# mouthbrain.net
KiCad netlist of a schematic drawn in EAGLE
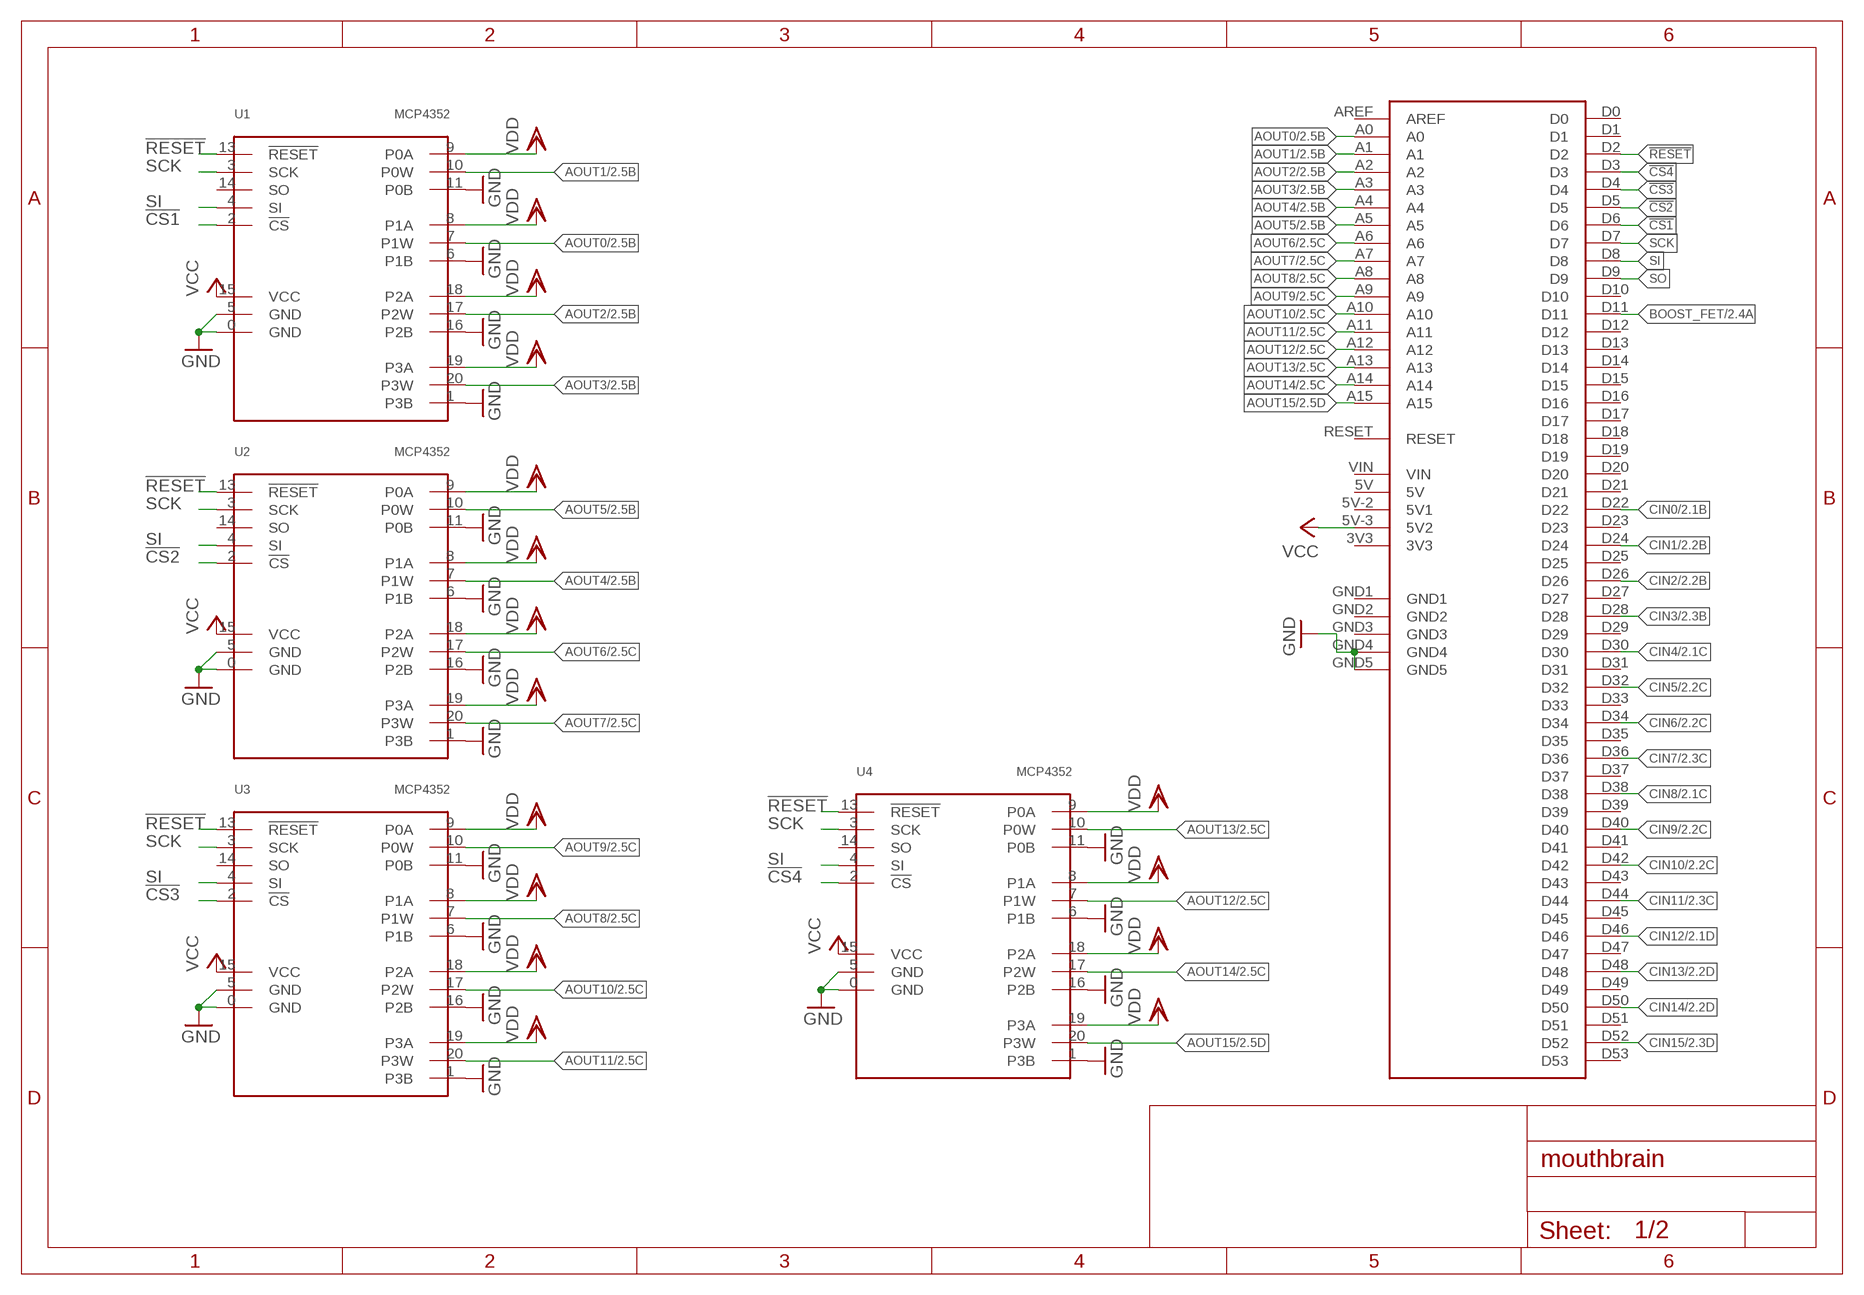
[diagram p0: schematic, sheet 1]
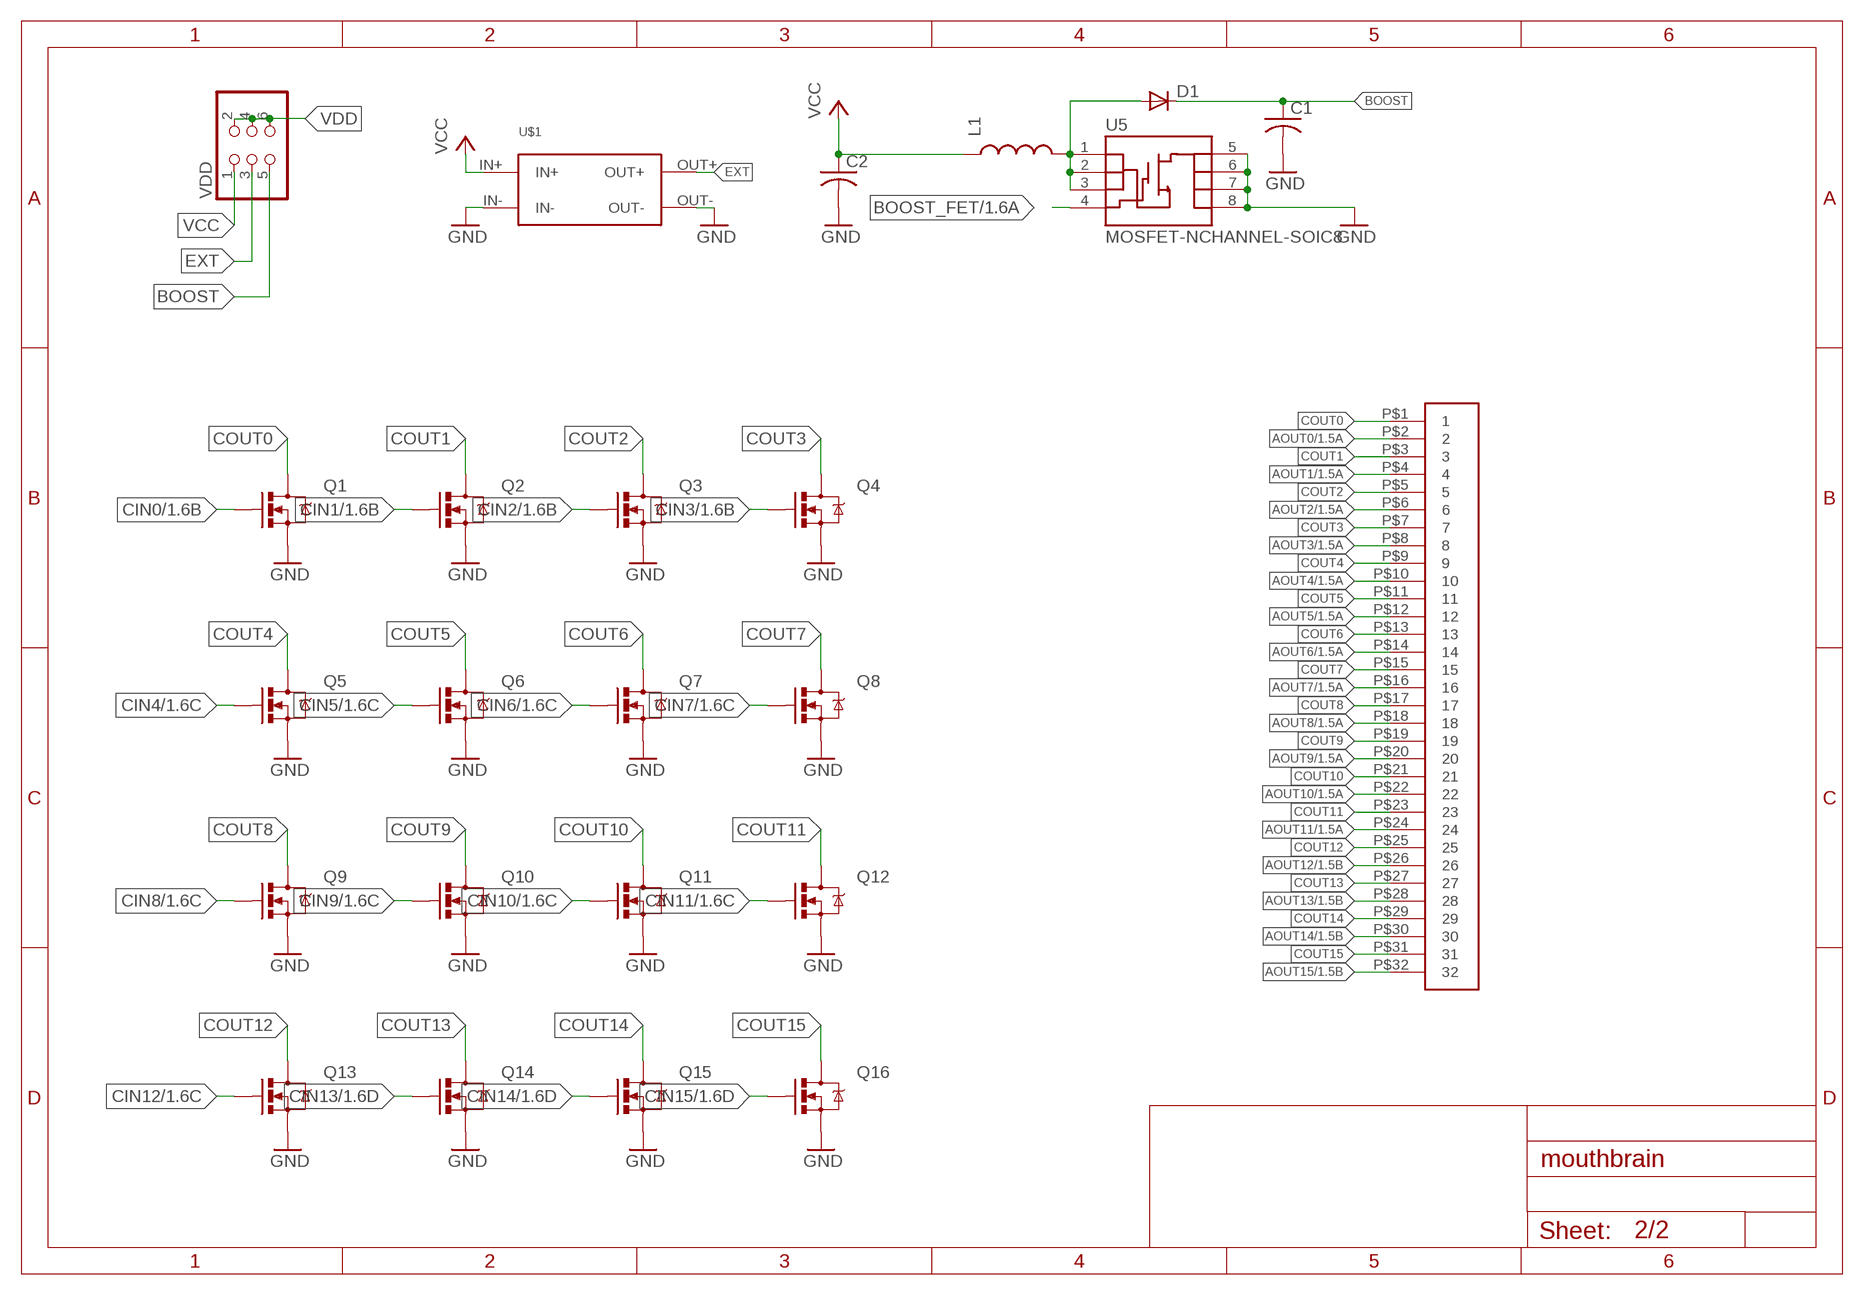
[diagram p1: schematic, sheet 2]

(export (version "E")
  (design (tool "Eeschema 10.0.6"))
  (components
    (comp (ref "C1")
      (value "C-USC1206")
      (footprint "eagle-import:C1206")
      (libsource (lib "eagle-import") (part "C-USC1206"))
    )
    (comp (ref "C2")
      (value "C-USC1206")
      (footprint "eagle-import:C1206")
      (libsource (lib "eagle-import") (part "C-USC1206"))
    )
    (comp (ref "D1")
      (value "DIODESMA")
      (footprint "eagle-import:SMA-DIODE")
      (libsource (lib "eagle-import") (part "DIODESMA"))
    )
    (comp (ref "L1")
      (value "INDUCTOR1206H*")
      (footprint "eagle-import:INDUCTOR-1206")
      (libsource (lib "eagle-import") (part "INDUCTORH1206"))
    )
    (comp (ref "Q1")
      (value "MOSFET-NCHANNELSMD")
      (footprint "eagle-import:SOT23-3")
      (libsource (lib "eagle-import") (part "MOSFET-NCHANNELSMD"))
    )
    (comp (ref "Q2")
      (value "MOSFET-NCHANNELSMD")
      (footprint "eagle-import:SOT23-3")
      (libsource (lib "eagle-import") (part "MOSFET-NCHANNELSMD"))
    )
    (comp (ref "Q3")
      (value "MOSFET-NCHANNELSMD")
      (footprint "eagle-import:SOT23-3")
      (libsource (lib "eagle-import") (part "MOSFET-NCHANNELSMD"))
    )
    (comp (ref "Q4")
      (value "MOSFET-NCHANNELSMD")
      (footprint "eagle-import:SOT23-3")
      (libsource (lib "eagle-import") (part "MOSFET-NCHANNELSMD"))
    )
    (comp (ref "Q5")
      (value "MOSFET-NCHANNELSMD")
      (footprint "eagle-import:SOT23-3")
      (libsource (lib "eagle-import") (part "MOSFET-NCHANNELSMD"))
    )
    (comp (ref "Q6")
      (value "MOSFET-NCHANNELSMD")
      (footprint "eagle-import:SOT23-3")
      (libsource (lib "eagle-import") (part "MOSFET-NCHANNELSMD"))
    )
    (comp (ref "Q7")
      (value "MOSFET-NCHANNELSMD")
      (footprint "eagle-import:SOT23-3")
      (libsource (lib "eagle-import") (part "MOSFET-NCHANNELSMD"))
    )
    (comp (ref "Q8")
      (value "MOSFET-NCHANNELSMD")
      (footprint "eagle-import:SOT23-3")
      (libsource (lib "eagle-import") (part "MOSFET-NCHANNELSMD"))
    )
    (comp (ref "Q9")
      (value "MOSFET-NCHANNELSMD")
      (footprint "eagle-import:SOT23-3")
      (libsource (lib "eagle-import") (part "MOSFET-NCHANNELSMD"))
    )
    (comp (ref "Q10")
      (value "MOSFET-NCHANNELSMD")
      (footprint "eagle-import:SOT23-3")
      (libsource (lib "eagle-import") (part "MOSFET-NCHANNELSMD"))
    )
    (comp (ref "Q11")
      (value "MOSFET-NCHANNELSMD")
      (footprint "eagle-import:SOT23-3")
      (libsource (lib "eagle-import") (part "MOSFET-NCHANNELSMD"))
    )
    (comp (ref "Q12")
      (value "MOSFET-NCHANNELSMD")
      (footprint "eagle-import:SOT23-3")
      (libsource (lib "eagle-import") (part "MOSFET-NCHANNELSMD"))
    )
    (comp (ref "Q13")
      (value "MOSFET-NCHANNELSMD")
      (footprint "eagle-import:SOT23-3")
      (libsource (lib "eagle-import") (part "MOSFET-NCHANNELSMD"))
    )
    (comp (ref "Q14")
      (value "MOSFET-NCHANNELSMD")
      (footprint "eagle-import:SOT23-3")
      (libsource (lib "eagle-import") (part "MOSFET-NCHANNELSMD"))
    )
    (comp (ref "Q15")
      (value "MOSFET-NCHANNELSMD")
      (footprint "eagle-import:SOT23-3")
      (libsource (lib "eagle-import") (part "MOSFET-NCHANNELSMD"))
    )
    (comp (ref "Q16")
      (value "MOSFET-NCHANNELSMD")
      (footprint "eagle-import:SOT23-3")
      (libsource (lib "eagle-import") (part "MOSFET-NCHANNELSMD"))
    )
    (comp (ref "U$1")
      (value "DC-DC-CONVERTER")
      (footprint "eagle-import:DC-DC-MODULE")
      (libsource (lib "eagle-import") (part "DC-DC-CONVERTER"))
    )
    (comp (ref "U$2")
      (value "FPC-0.5-32HORIZ")
      (footprint "eagle-import:FPC-32-HORIZONTAL")
      (libsource (lib "eagle-import") (part "FPC-0.5-32HORIZ"))
    )
    (comp (ref "U5")
      (value "MOSFET-NCHANNEL-SOIC8")
      (footprint "eagle-import:SO08")
      (libsource (lib "eagle-import") (part "MOSFET-NCHANNEL-SOIC8"))
    )
    (comp (ref "VDD")
      (value "PINHD-2X3")
      (footprint "eagle-import:2X03")
      (libsource (lib "eagle-import") (part "PINHD-2X3"))
    )
    (comp (ref "U$3")
      (value "ARDUINO-MEGA")
      (footprint "eagle-import:ARDUINO-MEGA")
      (libsource (lib "eagle-import") (part "ARDUINO-MEGA"))
    )
    (comp (ref "U1")
      (value "MCP4352")
      (footprint "eagle-import:QFN-20-PAD")
      (libsource (lib "eagle-import") (part "MCP4352"))
    )
    (comp (ref "U2")
      (value "MCP4352")
      (footprint "eagle-import:QFN-20-PAD")
      (libsource (lib "eagle-import") (part "MCP4352"))
    )
    (comp (ref "U3")
      (value "MCP4352")
      (footprint "eagle-import:QFN-20-PAD")
      (libsource (lib "eagle-import") (part "MCP4352"))
    )
    (comp (ref "U4")
      (value "MCP4352")
      (footprint "eagle-import:QFN-20-PAD")
      (libsource (lib "eagle-import") (part "MCP4352"))
    )
  )
  (nets
    (net (code "1") (name "AOUT0") (class "Default")
      (node (ref "U$2") (pin "P$2") (pinfunction "2_P$2") (pintype "bidirectional"))
      (node (ref "U$3") (pin "A0") (pinfunction "A0_A0") (pintype "bidirectional"))
      (node (ref "U1") (pin "7") (pinfunction "P1W_7") (pintype "bidirectional"))
    )
    (net (code "2") (name "AOUT1") (class "Default")
      (node (ref "U$2") (pin "P$4") (pinfunction "4_P$4") (pintype "bidirectional"))
      (node (ref "U$3") (pin "A1") (pinfunction "A1_A1") (pintype "bidirectional"))
      (node (ref "U1") (pin "10") (pinfunction "P0W_10") (pintype "bidirectional"))
    )
    (net (code "3") (name "AOUT2") (class "Default")
      (node (ref "U$2") (pin "P$6") (pinfunction "6_P$6") (pintype "bidirectional"))
      (node (ref "U$3") (pin "A2") (pinfunction "A2_A2") (pintype "bidirectional"))
      (node (ref "U1") (pin "17") (pinfunction "P2W_17") (pintype "bidirectional"))
    )
    (net (code "4") (name "AOUT3") (class "Default")
      (node (ref "U$2") (pin "P$8") (pinfunction "8_P$8") (pintype "bidirectional"))
      (node (ref "U$3") (pin "A3") (pinfunction "A3_A3") (pintype "bidirectional"))
      (node (ref "U1") (pin "20") (pinfunction "P3W_20") (pintype "bidirectional"))
    )
    (net (code "5") (name "AOUT4") (class "Default")
      (node (ref "U$2") (pin "P$10") (pinfunction "10_P$10") (pintype "bidirectional"))
      (node (ref "U$3") (pin "A4") (pinfunction "A4_A4") (pintype "bidirectional"))
      (node (ref "U2") (pin "7") (pinfunction "P1W_7") (pintype "bidirectional"))
    )
    (net (code "6") (name "AOUT5") (class "Default")
      (node (ref "U$2") (pin "P$12") (pinfunction "12_P$12") (pintype "bidirectional"))
      (node (ref "U$3") (pin "A5") (pinfunction "A5_A5") (pintype "bidirectional"))
      (node (ref "U2") (pin "10") (pinfunction "P0W_10") (pintype "bidirectional"))
    )
    (net (code "7") (name "AOUT6") (class "Default")
      (node (ref "U$2") (pin "P$14") (pinfunction "14_P$14") (pintype "bidirectional"))
      (node (ref "U$3") (pin "A6") (pinfunction "A6_A6") (pintype "bidirectional"))
      (node (ref "U2") (pin "17") (pinfunction "P2W_17") (pintype "bidirectional"))
    )
    (net (code "8") (name "AOUT7") (class "Default")
      (node (ref "U$2") (pin "P$16") (pinfunction "16_P$16") (pintype "bidirectional"))
      (node (ref "U$3") (pin "A7") (pinfunction "A7_A7") (pintype "bidirectional"))
      (node (ref "U2") (pin "20") (pinfunction "P3W_20") (pintype "bidirectional"))
    )
    (net (code "9") (name "AOUT8") (class "Default")
      (node (ref "U$2") (pin "P$18") (pinfunction "18_P$18") (pintype "bidirectional"))
      (node (ref "U$3") (pin "A8") (pinfunction "A8_A8") (pintype "bidirectional"))
      (node (ref "U3") (pin "7") (pinfunction "P1W_7") (pintype "bidirectional"))
    )
    (net (code "10") (name "AOUT9") (class "Default")
      (node (ref "U$2") (pin "P$20") (pinfunction "20_P$20") (pintype "bidirectional"))
      (node (ref "U$3") (pin "A9") (pinfunction "A9_A9") (pintype "bidirectional"))
      (node (ref "U3") (pin "10") (pinfunction "P0W_10") (pintype "bidirectional"))
    )
    (net (code "11") (name "AOUT10") (class "Default")
      (node (ref "U$2") (pin "P$22") (pinfunction "22_P$22") (pintype "bidirectional"))
      (node (ref "U$3") (pin "A10") (pinfunction "A10_A10") (pintype "bidirectional"))
      (node (ref "U3") (pin "17") (pinfunction "P2W_17") (pintype "bidirectional"))
    )
    (net (code "12") (name "AOUT11") (class "Default")
      (node (ref "U$2") (pin "P$24") (pinfunction "24_P$24") (pintype "bidirectional"))
      (node (ref "U$3") (pin "A11") (pinfunction "A11_A11") (pintype "bidirectional"))
      (node (ref "U3") (pin "20") (pinfunction "P3W_20") (pintype "bidirectional"))
    )
    (net (code "13") (name "AOUT12") (class "Default")
      (node (ref "U$2") (pin "P$26") (pinfunction "26_P$26") (pintype "bidirectional"))
      (node (ref "U$3") (pin "A12") (pinfunction "A12_A12") (pintype "bidirectional"))
      (node (ref "U4") (pin "7") (pinfunction "P1W_7") (pintype "bidirectional"))
    )
    (net (code "14") (name "AOUT13") (class "Default")
      (node (ref "U$2") (pin "P$28") (pinfunction "28_P$28") (pintype "bidirectional"))
      (node (ref "U$3") (pin "A13") (pinfunction "A13_A13") (pintype "bidirectional"))
      (node (ref "U4") (pin "10") (pinfunction "P0W_10") (pintype "bidirectional"))
    )
    (net (code "15") (name "AOUT14") (class "Default")
      (node (ref "U$2") (pin "P$30") (pinfunction "30_P$30") (pintype "bidirectional"))
      (node (ref "U$3") (pin "A14") (pinfunction "A14_A14") (pintype "bidirectional"))
      (node (ref "U4") (pin "17") (pinfunction "P2W_17") (pintype "bidirectional"))
    )
    (net (code "16") (name "AOUT15") (class "Default")
      (node (ref "U$2") (pin "P$32") (pinfunction "32_P$32") (pintype "bidirectional"))
      (node (ref "U$3") (pin "A15") (pinfunction "A15_A15") (pintype "bidirectional"))
      (node (ref "U4") (pin "20") (pinfunction "P3W_20") (pintype "bidirectional"))
    )
    (net (code "17") (name "BOOST") (class "Default")
      (node (ref "C1") (pin "1") (pinfunction "1_1") (pintype "passive"))
      (node (ref "D1") (pin "C") (pinfunction "C_C") (pintype "passive"))
      (node (ref "VDD") (pin "5") (pinfunction "5_5") (pintype "passive"))
    )
    (net (code "18") (name "BOOST_FET") (class "Default")
      (node (ref "U$3") (pin "D11") (pinfunction "D11_D11") (pintype "bidirectional"))
      (node (ref "U5") (pin "4") (pinfunction "G_4") (pintype "bidirectional"))
    )
    (net (code "19") (name "CIN0") (class "Default")
      (node (ref "Q1") (pin "1") (pinfunction "G_1") (pintype "passive"))
      (node (ref "U$3") (pin "D22") (pinfunction "D22_D22") (pintype "bidirectional"))
    )
    (net (code "20") (name "CIN1") (class "Default")
      (node (ref "Q2") (pin "1") (pinfunction "G_1") (pintype "passive"))
      (node (ref "U$3") (pin "D24") (pinfunction "D24_D24") (pintype "bidirectional"))
    )
    (net (code "21") (name "CIN2") (class "Default")
      (node (ref "Q3") (pin "1") (pinfunction "G_1") (pintype "passive"))
      (node (ref "U$3") (pin "D26") (pinfunction "D26_D26") (pintype "bidirectional"))
    )
    (net (code "22") (name "CIN3") (class "Default")
      (node (ref "Q4") (pin "1") (pinfunction "G_1") (pintype "passive"))
      (node (ref "U$3") (pin "D28") (pinfunction "D28_D28") (pintype "bidirectional"))
    )
    (net (code "23") (name "CIN4") (class "Default")
      (node (ref "Q5") (pin "1") (pinfunction "G_1") (pintype "passive"))
      (node (ref "U$3") (pin "D30") (pinfunction "D30_D30") (pintype "bidirectional"))
    )
    (net (code "24") (name "CIN5") (class "Default")
      (node (ref "Q6") (pin "1") (pinfunction "G_1") (pintype "passive"))
      (node (ref "U$3") (pin "D32") (pinfunction "D32_D32") (pintype "bidirectional"))
    )
    (net (code "25") (name "CIN6") (class "Default")
      (node (ref "Q7") (pin "1") (pinfunction "G_1") (pintype "passive"))
      (node (ref "U$3") (pin "D34") (pinfunction "D34_D34") (pintype "bidirectional"))
    )
    (net (code "26") (name "CIN7") (class "Default")
      (node (ref "Q8") (pin "1") (pinfunction "G_1") (pintype "passive"))
      (node (ref "U$3") (pin "D36") (pinfunction "D36_D36") (pintype "bidirectional"))
    )
    (net (code "27") (name "CIN8") (class "Default")
      (node (ref "Q9") (pin "1") (pinfunction "G_1") (pintype "passive"))
      (node (ref "U$3") (pin "D38") (pinfunction "D38_D38") (pintype "bidirectional"))
    )
    (net (code "28") (name "CIN9") (class "Default")
      (node (ref "Q10") (pin "1") (pinfunction "G_1") (pintype "passive"))
      (node (ref "U$3") (pin "D40") (pinfunction "D40_D40") (pintype "bidirectional"))
    )
    (net (code "29") (name "CIN10") (class "Default")
      (node (ref "Q11") (pin "1") (pinfunction "G_1") (pintype "passive"))
      (node (ref "U$3") (pin "D42") (pinfunction "D42_D42") (pintype "bidirectional"))
    )
    (net (code "30") (name "CIN11") (class "Default")
      (node (ref "Q12") (pin "1") (pinfunction "G_1") (pintype "passive"))
      (node (ref "U$3") (pin "D44") (pinfunction "D44_D44") (pintype "bidirectional"))
    )
    (net (code "31") (name "CIN12") (class "Default")
      (node (ref "Q13") (pin "1") (pinfunction "G_1") (pintype "passive"))
      (node (ref "U$3") (pin "D46") (pinfunction "D46_D46") (pintype "bidirectional"))
    )
    (net (code "32") (name "CIN13") (class "Default")
      (node (ref "Q14") (pin "1") (pinfunction "G_1") (pintype "passive"))
      (node (ref "U$3") (pin "D48") (pinfunction "D48_D48") (pintype "bidirectional"))
    )
    (net (code "33") (name "CIN14") (class "Default")
      (node (ref "Q15") (pin "1") (pinfunction "G_1") (pintype "passive"))
      (node (ref "U$3") (pin "D50") (pinfunction "D50_D50") (pintype "bidirectional"))
    )
    (net (code "34") (name "CIN15") (class "Default")
      (node (ref "Q16") (pin "1") (pinfunction "G_1") (pintype "passive"))
      (node (ref "U$3") (pin "D52") (pinfunction "D52_D52") (pintype "bidirectional"))
    )
    (net (code "35") (name "COUT0") (class "Default")
      (node (ref "Q1") (pin "3") (pinfunction "D_3") (pintype "passive"))
      (node (ref "U$2") (pin "P$1") (pinfunction "1_P$1") (pintype "bidirectional"))
    )
    (net (code "36") (name "COUT1") (class "Default")
      (node (ref "Q2") (pin "3") (pinfunction "D_3") (pintype "passive"))
      (node (ref "U$2") (pin "P$3") (pinfunction "3_P$3") (pintype "bidirectional"))
    )
    (net (code "37") (name "COUT2") (class "Default")
      (node (ref "Q3") (pin "3") (pinfunction "D_3") (pintype "passive"))
      (node (ref "U$2") (pin "P$5") (pinfunction "5_P$5") (pintype "bidirectional"))
    )
    (net (code "38") (name "COUT3") (class "Default")
      (node (ref "Q4") (pin "3") (pinfunction "D_3") (pintype "passive"))
      (node (ref "U$2") (pin "P$7") (pinfunction "7_P$7") (pintype "bidirectional"))
    )
    (net (code "39") (name "COUT4") (class "Default")
      (node (ref "Q5") (pin "3") (pinfunction "D_3") (pintype "passive"))
      (node (ref "U$2") (pin "P$9") (pinfunction "9_P$9") (pintype "bidirectional"))
    )
    (net (code "40") (name "COUT5") (class "Default")
      (node (ref "Q6") (pin "3") (pinfunction "D_3") (pintype "passive"))
      (node (ref "U$2") (pin "P$11") (pinfunction "11_P$11") (pintype "bidirectional"))
    )
    (net (code "41") (name "COUT6") (class "Default")
      (node (ref "Q7") (pin "3") (pinfunction "D_3") (pintype "passive"))
      (node (ref "U$2") (pin "P$13") (pinfunction "13_P$13") (pintype "bidirectional"))
    )
    (net (code "42") (name "COUT7") (class "Default")
      (node (ref "Q8") (pin "3") (pinfunction "D_3") (pintype "passive"))
      (node (ref "U$2") (pin "P$15") (pinfunction "15_P$15") (pintype "bidirectional"))
    )
    (net (code "43") (name "COUT8") (class "Default")
      (node (ref "Q9") (pin "3") (pinfunction "D_3") (pintype "passive"))
      (node (ref "U$2") (pin "P$17") (pinfunction "17_P$17") (pintype "bidirectional"))
    )
    (net (code "44") (name "COUT9") (class "Default")
      (node (ref "Q10") (pin "3") (pinfunction "D_3") (pintype "passive"))
      (node (ref "U$2") (pin "P$19") (pinfunction "19_P$19") (pintype "bidirectional"))
    )
    (net (code "45") (name "COUT10") (class "Default")
      (node (ref "Q11") (pin "3") (pinfunction "D_3") (pintype "passive"))
      (node (ref "U$2") (pin "P$21") (pinfunction "21_P$21") (pintype "bidirectional"))
    )
    (net (code "46") (name "COUT11") (class "Default")
      (node (ref "Q12") (pin "3") (pinfunction "D_3") (pintype "passive"))
      (node (ref "U$2") (pin "P$23") (pinfunction "23_P$23") (pintype "bidirectional"))
    )
    (net (code "47") (name "COUT12") (class "Default")
      (node (ref "Q13") (pin "3") (pinfunction "D_3") (pintype "passive"))
      (node (ref "U$2") (pin "P$25") (pinfunction "25_P$25") (pintype "bidirectional"))
    )
    (net (code "48") (name "COUT13") (class "Default")
      (node (ref "Q14") (pin "3") (pinfunction "D_3") (pintype "passive"))
      (node (ref "U$2") (pin "P$27") (pinfunction "27_P$27") (pintype "bidirectional"))
    )
    (net (code "49") (name "COUT14") (class "Default")
      (node (ref "Q15") (pin "3") (pinfunction "D_3") (pintype "passive"))
      (node (ref "U$2") (pin "P$29") (pinfunction "29_P$29") (pintype "bidirectional"))
    )
    (net (code "50") (name "COUT15") (class "Default")
      (node (ref "Q16") (pin "3") (pinfunction "D_3") (pintype "passive"))
      (node (ref "U$2") (pin "P$31") (pinfunction "31_P$31") (pintype "bidirectional"))
    )
    (net (code "51") (name "EXT") (class "Default")
      (node (ref "U$1") (pin "OUT+") (pinfunction "OUT+_OUT+") (pintype "bidirectional"))
      (node (ref "VDD") (pin "3") (pinfunction "3_3") (pintype "passive"))
    )
    (net (code "52") (name "GND") (class "Default")
      (node (ref "C1") (pin "2") (pinfunction "2_2") (pintype "passive"))
      (node (ref "C2") (pin "2") (pinfunction "2_2") (pintype "passive"))
      (node (ref "Q1") (pin "2") (pinfunction "S_2") (pintype "passive"))
      (node (ref "Q10") (pin "2") (pinfunction "S_2") (pintype "passive"))
      (node (ref "Q11") (pin "2") (pinfunction "S_2") (pintype "passive"))
      (node (ref "Q12") (pin "2") (pinfunction "S_2") (pintype "passive"))
      (node (ref "Q13") (pin "2") (pinfunction "S_2") (pintype "passive"))
      (node (ref "Q14") (pin "2") (pinfunction "S_2") (pintype "passive"))
      (node (ref "Q15") (pin "2") (pinfunction "S_2") (pintype "passive"))
      (node (ref "Q16") (pin "2") (pinfunction "S_2") (pintype "passive"))
      (node (ref "Q2") (pin "2") (pinfunction "S_2") (pintype "passive"))
      (node (ref "Q3") (pin "2") (pinfunction "S_2") (pintype "passive"))
      (node (ref "Q4") (pin "2") (pinfunction "S_2") (pintype "passive"))
      (node (ref "Q5") (pin "2") (pinfunction "S_2") (pintype "passive"))
      (node (ref "Q6") (pin "2") (pinfunction "S_2") (pintype "passive"))
      (node (ref "Q7") (pin "2") (pinfunction "S_2") (pintype "passive"))
      (node (ref "Q8") (pin "2") (pinfunction "S_2") (pintype "passive"))
      (node (ref "Q9") (pin "2") (pinfunction "S_2") (pintype "passive"))
      (node (ref "U$1") (pin "IN-") (pinfunction "IN-_IN-") (pintype "bidirectional"))
      (node (ref "U$1") (pin "OUT-") (pinfunction "OUT-_OUT-") (pintype "bidirectional"))
      (node (ref "U$3") (pin "GND4") (pinfunction "GND4_GND4") (pintype "bidirectional"))
      (node (ref "U$3") (pin "GND5") (pinfunction "GND5_GND5") (pintype "bidirectional"))
      (node (ref "U1") (pin "0") (pinfunction "GND_0") (pintype "bidirectional"))
      (node (ref "U1") (pin "1") (pinfunction "P3B_1") (pintype "bidirectional"))
      (node (ref "U1") (pin "11") (pinfunction "P0B_11") (pintype "bidirectional"))
      (node (ref "U1") (pin "16") (pinfunction "P2B_16") (pintype "bidirectional"))
      (node (ref "U1") (pin "5") (pinfunction "GND_5") (pintype "bidirectional"))
      (node (ref "U1") (pin "6") (pinfunction "P1B_6") (pintype "bidirectional"))
      (node (ref "U2") (pin "0") (pinfunction "GND_0") (pintype "bidirectional"))
      (node (ref "U2") (pin "1") (pinfunction "P3B_1") (pintype "bidirectional"))
      (node (ref "U2") (pin "11") (pinfunction "P0B_11") (pintype "bidirectional"))
      (node (ref "U2") (pin "16") (pinfunction "P2B_16") (pintype "bidirectional"))
      (node (ref "U2") (pin "5") (pinfunction "GND_5") (pintype "bidirectional"))
      (node (ref "U2") (pin "6") (pinfunction "P1B_6") (pintype "bidirectional"))
      (node (ref "U3") (pin "0") (pinfunction "GND_0") (pintype "bidirectional"))
      (node (ref "U3") (pin "1") (pinfunction "P3B_1") (pintype "bidirectional"))
      (node (ref "U3") (pin "11") (pinfunction "P0B_11") (pintype "bidirectional"))
      (node (ref "U3") (pin "16") (pinfunction "P2B_16") (pintype "bidirectional"))
      (node (ref "U3") (pin "5") (pinfunction "GND_5") (pintype "bidirectional"))
      (node (ref "U3") (pin "6") (pinfunction "P1B_6") (pintype "bidirectional"))
      (node (ref "U4") (pin "0") (pinfunction "GND_0") (pintype "bidirectional"))
      (node (ref "U4") (pin "1") (pinfunction "P3B_1") (pintype "bidirectional"))
      (node (ref "U4") (pin "11") (pinfunction "P0B_11") (pintype "bidirectional"))
      (node (ref "U4") (pin "16") (pinfunction "P2B_16") (pintype "bidirectional"))
      (node (ref "U4") (pin "5") (pinfunction "GND_5") (pintype "bidirectional"))
      (node (ref "U4") (pin "6") (pinfunction "P1B_6") (pintype "bidirectional"))
      (node (ref "U5") (pin "5") (pinfunction "D_5") (pintype "bidirectional"))
      (node (ref "U5") (pin "6") (pinfunction "D_6") (pintype "bidirectional"))
      (node (ref "U5") (pin "7") (pinfunction "D_7") (pintype "bidirectional"))
      (node (ref "U5") (pin "8") (pinfunction "D_8") (pintype "bidirectional"))
    )
    (net (code "53") (name "Net-(L1-2)") (class "Default")
      (node (ref "D1") (pin "A") (pinfunction "A_A") (pintype "passive"))
      (node (ref "L1") (pin "P$2") (pinfunction "2_P$2") (pintype "passive"))
      (node (ref "U5") (pin "1") (pinfunction "S_1") (pintype "bidirectional"))
      (node (ref "U5") (pin "2") (pinfunction "S_2") (pintype "bidirectional"))
      (node (ref "U5") (pin "3") (pinfunction "S_3") (pintype "bidirectional"))
    )
    (net (code "54") (name "SCK") (class "Default")
      (node (ref "U$3") (pin "D7") (pinfunction "D7_D7") (pintype "bidirectional"))
      (node (ref "U1") (pin "3") (pinfunction "SCK_3") (pintype "bidirectional"))
      (node (ref "U2") (pin "3") (pinfunction "SCK_3") (pintype "bidirectional"))
      (node (ref "U3") (pin "3") (pinfunction "SCK_3") (pintype "bidirectional"))
      (node (ref "U4") (pin "3") (pinfunction "SCK_3") (pintype "bidirectional"))
    )
    (net (code "55") (name "SI") (class "Default")
      (node (ref "U$3") (pin "D8") (pinfunction "D8_D8") (pintype "bidirectional"))
      (node (ref "U1") (pin "4") (pinfunction "SI_4") (pintype "bidirectional"))
      (node (ref "U2") (pin "4") (pinfunction "SI_4") (pintype "bidirectional"))
      (node (ref "U3") (pin "4") (pinfunction "SI_4") (pintype "bidirectional"))
      (node (ref "U4") (pin "4") (pinfunction "SI_4") (pintype "bidirectional"))
    )
    (net (code "56") (name "SO") (class "Default")
      (node (ref "U$3") (pin "D9") (pinfunction "D9_D9") (pintype "bidirectional"))
    )
    (net (code "57") (name "VCC") (class "Default")
      (node (ref "C2") (pin "1") (pinfunction "1_1") (pintype "passive"))
      (node (ref "L1") (pin "P$1") (pinfunction "1_P$1") (pintype "passive"))
      (node (ref "U$1") (pin "IN+") (pinfunction "IN+_IN+") (pintype "bidirectional"))
      (node (ref "U$3") (pin "5V-3") (pinfunction "5V2_5V-3") (pintype "bidirectional"))
      (node (ref "U1") (pin "15") (pinfunction "VCC_15") (pintype "bidirectional"))
      (node (ref "U2") (pin "15") (pinfunction "VCC_15") (pintype "bidirectional"))
      (node (ref "U3") (pin "15") (pinfunction "VCC_15") (pintype "bidirectional"))
      (node (ref "U4") (pin "15") (pinfunction "VCC_15") (pintype "bidirectional"))
      (node (ref "VDD") (pin "1") (pinfunction "1_1") (pintype "passive"))
    )
    (net (code "58") (name "VDD") (class "Default")
      (node (ref "U1") (pin "18") (pinfunction "P2A_18") (pintype "bidirectional"))
      (node (ref "U1") (pin "19") (pinfunction "P3A_19") (pintype "bidirectional"))
      (node (ref "U1") (pin "8") (pinfunction "P1A_8") (pintype "bidirectional"))
      (node (ref "U1") (pin "9") (pinfunction "P0A_9") (pintype "bidirectional"))
      (node (ref "U2") (pin "18") (pinfunction "P2A_18") (pintype "bidirectional"))
      (node (ref "U2") (pin "19") (pinfunction "P3A_19") (pintype "bidirectional"))
      (node (ref "U2") (pin "8") (pinfunction "P1A_8") (pintype "bidirectional"))
      (node (ref "U2") (pin "9") (pinfunction "P0A_9") (pintype "bidirectional"))
      (node (ref "U3") (pin "18") (pinfunction "P2A_18") (pintype "bidirectional"))
      (node (ref "U3") (pin "19") (pinfunction "P3A_19") (pintype "bidirectional"))
      (node (ref "U3") (pin "8") (pinfunction "P1A_8") (pintype "bidirectional"))
      (node (ref "U3") (pin "9") (pinfunction "P0A_9") (pintype "bidirectional"))
      (node (ref "U4") (pin "18") (pinfunction "P2A_18") (pintype "bidirectional"))
      (node (ref "U4") (pin "19") (pinfunction "P3A_19") (pintype "bidirectional"))
      (node (ref "U4") (pin "8") (pinfunction "P1A_8") (pintype "bidirectional"))
      (node (ref "U4") (pin "9") (pinfunction "P0A_9") (pintype "bidirectional"))
      (node (ref "VDD") (pin "2") (pinfunction "2_2") (pintype "passive"))
      (node (ref "VDD") (pin "4") (pinfunction "4_4") (pintype "passive"))
      (node (ref "VDD") (pin "6") (pinfunction "6_6") (pintype "passive"))
    )
    (net (code "59") (name "unconnected-(U$3-5V1-Pad5V-2)") (class "Default")
      (node (ref "U$3") (pin "5V-2") (pinfunction "5V1_5V-2") (pintype "bidirectional"))
    )
    (net (code "60") (name "unconnected-(U$3-Pad3V3)") (class "Default")
      (node (ref "U$3") (pin "3V3") (pinfunction "3V3_3V3") (pintype "bidirectional"))
    )
    (net (code "61") (name "unconnected-(U$3-Pad5V)") (class "Default")
      (node (ref "U$3") (pin "5V") (pinfunction "5V_5V") (pintype "bidirectional"))
    )
    (net (code "62") (name "unconnected-(U$3-PadAREF)") (class "Default")
      (node (ref "U$3") (pin "AREF") (pinfunction "AREF_AREF") (pintype "bidirectional"))
    )
    (net (code "63") (name "unconnected-(U$3-PadD0)") (class "Default")
      (node (ref "U$3") (pin "D0") (pinfunction "D0_D0") (pintype "bidirectional"))
    )
    (net (code "64") (name "unconnected-(U$3-PadD1)") (class "Default")
      (node (ref "U$3") (pin "D1") (pinfunction "D1_D1") (pintype "bidirectional"))
    )
    (net (code "65") (name "unconnected-(U$3-PadD10)") (class "Default")
      (node (ref "U$3") (pin "D10") (pinfunction "D10_D10") (pintype "bidirectional"))
    )
    (net (code "66") (name "unconnected-(U$3-PadD12)") (class "Default")
      (node (ref "U$3") (pin "D12") (pinfunction "D12_D12") (pintype "bidirectional"))
    )
    (net (code "67") (name "unconnected-(U$3-PadD13)") (class "Default")
      (node (ref "U$3") (pin "D13") (pinfunction "D13_D13") (pintype "bidirectional"))
    )
    (net (code "68") (name "unconnected-(U$3-PadD14)") (class "Default")
      (node (ref "U$3") (pin "D14") (pinfunction "D14_D14") (pintype "bidirectional"))
    )
    (net (code "69") (name "unconnected-(U$3-PadD15)") (class "Default")
      (node (ref "U$3") (pin "D15") (pinfunction "D15_D15") (pintype "bidirectional"))
    )
    (net (code "70") (name "unconnected-(U$3-PadD16)") (class "Default")
      (node (ref "U$3") (pin "D16") (pinfunction "D16_D16") (pintype "bidirectional"))
    )
    (net (code "71") (name "unconnected-(U$3-PadD17)") (class "Default")
      (node (ref "U$3") (pin "D17") (pinfunction "D17_D17") (pintype "bidirectional"))
    )
    (net (code "72") (name "unconnected-(U$3-PadD18)") (class "Default")
      (node (ref "U$3") (pin "D18") (pinfunction "D18_D18") (pintype "bidirectional"))
    )
    (net (code "73") (name "unconnected-(U$3-PadD19)") (class "Default")
      (node (ref "U$3") (pin "D19") (pinfunction "D19_D19") (pintype "bidirectional"))
    )
    (net (code "74") (name "unconnected-(U$3-PadD20)") (class "Default")
      (node (ref "U$3") (pin "D20") (pinfunction "D20_D20") (pintype "bidirectional"))
    )
    (net (code "75") (name "unconnected-(U$3-PadD21)") (class "Default")
      (node (ref "U$3") (pin "D21") (pinfunction "D21_D21") (pintype "bidirectional"))
    )
    (net (code "76") (name "unconnected-(U$3-PadD23)") (class "Default")
      (node (ref "U$3") (pin "D23") (pinfunction "D23_D23") (pintype "bidirectional"))
    )
    (net (code "77") (name "unconnected-(U$3-PadD25)") (class "Default")
      (node (ref "U$3") (pin "D25") (pinfunction "D25_D25") (pintype "bidirectional"))
    )
    (net (code "78") (name "unconnected-(U$3-PadD27)") (class "Default")
      (node (ref "U$3") (pin "D27") (pinfunction "D27_D27") (pintype "bidirectional"))
    )
    (net (code "79") (name "unconnected-(U$3-PadD29)") (class "Default")
      (node (ref "U$3") (pin "D29") (pinfunction "D29_D29") (pintype "bidirectional"))
    )
    (net (code "80") (name "unconnected-(U$3-PadD31)") (class "Default")
      (node (ref "U$3") (pin "D31") (pinfunction "D31_D31") (pintype "bidirectional"))
    )
    (net (code "81") (name "unconnected-(U$3-PadD33)") (class "Default")
      (node (ref "U$3") (pin "D33") (pinfunction "D33_D33") (pintype "bidirectional"))
    )
    (net (code "82") (name "unconnected-(U$3-PadD35)") (class "Default")
      (node (ref "U$3") (pin "D35") (pinfunction "D35_D35") (pintype "bidirectional"))
    )
    (net (code "83") (name "unconnected-(U$3-PadD37)") (class "Default")
      (node (ref "U$3") (pin "D37") (pinfunction "D37_D37") (pintype "bidirectional"))
    )
    (net (code "84") (name "unconnected-(U$3-PadD39)") (class "Default")
      (node (ref "U$3") (pin "D39") (pinfunction "D39_D39") (pintype "bidirectional"))
    )
    (net (code "85") (name "unconnected-(U$3-PadD41)") (class "Default")
      (node (ref "U$3") (pin "D41") (pinfunction "D41_D41") (pintype "bidirectional"))
    )
    (net (code "86") (name "unconnected-(U$3-PadD43)") (class "Default")
      (node (ref "U$3") (pin "D43") (pinfunction "D43_D43") (pintype "bidirectional"))
    )
    (net (code "87") (name "unconnected-(U$3-PadD45)") (class "Default")
      (node (ref "U$3") (pin "D45") (pinfunction "D45_D45") (pintype "bidirectional"))
    )
    (net (code "88") (name "unconnected-(U$3-PadD47)") (class "Default")
      (node (ref "U$3") (pin "D47") (pinfunction "D47_D47") (pintype "bidirectional"))
    )
    (net (code "89") (name "unconnected-(U$3-PadD49)") (class "Default")
      (node (ref "U$3") (pin "D49") (pinfunction "D49_D49") (pintype "bidirectional"))
    )
    (net (code "90") (name "unconnected-(U$3-PadD51)") (class "Default")
      (node (ref "U$3") (pin "D51") (pinfunction "D51_D51") (pintype "bidirectional"))
    )
    (net (code "91") (name "unconnected-(U$3-PadD53)") (class "Default")
      (node (ref "U$3") (pin "D53") (pinfunction "D53_D53") (pintype "bidirectional"))
    )
    (net (code "92") (name "unconnected-(U$3-PadGND1)") (class "Default")
      (node (ref "U$3") (pin "GND1") (pinfunction "GND1_GND1") (pintype "bidirectional"))
    )
    (net (code "93") (name "unconnected-(U$3-PadGND2)") (class "Default")
      (node (ref "U$3") (pin "GND2") (pinfunction "GND2_GND2") (pintype "bidirectional"))
    )
    (net (code "94") (name "unconnected-(U$3-PadGND3)") (class "Default")
      (node (ref "U$3") (pin "GND3") (pinfunction "GND3_GND3") (pintype "bidirectional"))
    )
    (net (code "95") (name "unconnected-(U$3-PadRESET)") (class "Default")
      (node (ref "U$3") (pin "RESET") (pinfunction "RESET_RESET") (pintype "bidirectional"))
    )
    (net (code "96") (name "unconnected-(U$3-PadVIN)") (class "Default")
      (node (ref "U$3") (pin "VIN") (pinfunction "VIN_VIN") (pintype "bidirectional"))
    )
    (net (code "97") (name "unconnected-(U1-SO-Pad14)") (class "Default")
      (node (ref "U1") (pin "14") (pinfunction "SO_14") (pintype "bidirectional"))
    )
    (net (code "98") (name "unconnected-(U2-SO-Pad14)") (class "Default")
      (node (ref "U2") (pin "14") (pinfunction "SO_14") (pintype "bidirectional"))
    )
    (net (code "99") (name "unconnected-(U3-SO-Pad14)") (class "Default")
      (node (ref "U3") (pin "14") (pinfunction "SO_14") (pintype "bidirectional"))
    )
    (net (code "100") (name "unconnected-(U4-SO-Pad14)") (class "Default")
      (node (ref "U4") (pin "14") (pinfunction "SO_14") (pintype "bidirectional"))
    )
    (net (code "101") (name "~{CS1}") (class "Default")
      (node (ref "U$3") (pin "D6") (pinfunction "D6_D6") (pintype "bidirectional"))
      (node (ref "U1") (pin "2") (pinfunction "~{CS}_2") (pintype "bidirectional"))
    )
    (net (code "102") (name "~{CS2}") (class "Default")
      (node (ref "U$3") (pin "D5") (pinfunction "D5_D5") (pintype "bidirectional"))
      (node (ref "U2") (pin "2") (pinfunction "~{CS}_2") (pintype "bidirectional"))
    )
    (net (code "103") (name "~{CS3}") (class "Default")
      (node (ref "U$3") (pin "D4") (pinfunction "D4_D4") (pintype "bidirectional"))
      (node (ref "U3") (pin "2") (pinfunction "~{CS}_2") (pintype "bidirectional"))
    )
    (net (code "104") (name "~{CS4}") (class "Default")
      (node (ref "U$3") (pin "D3") (pinfunction "D3_D3") (pintype "bidirectional"))
      (node (ref "U4") (pin "2") (pinfunction "~{CS}_2") (pintype "bidirectional"))
    )
    (net (code "105") (name "~{RESET}") (class "Default")
      (node (ref "U$3") (pin "D2") (pinfunction "D2_D2") (pintype "bidirectional"))
      (node (ref "U1") (pin "13") (pinfunction "~{RESET}_13") (pintype "bidirectional"))
      (node (ref "U2") (pin "13") (pinfunction "~{RESET}_13") (pintype "bidirectional"))
      (node (ref "U3") (pin "13") (pinfunction "~{RESET}_13") (pintype "bidirectional"))
      (node (ref "U4") (pin "13") (pinfunction "~{RESET}_13") (pintype "bidirectional"))
    )
  )
)
